# DCDC_Converter.net
KiCad netlist of a schematic drawn in Altium Designer
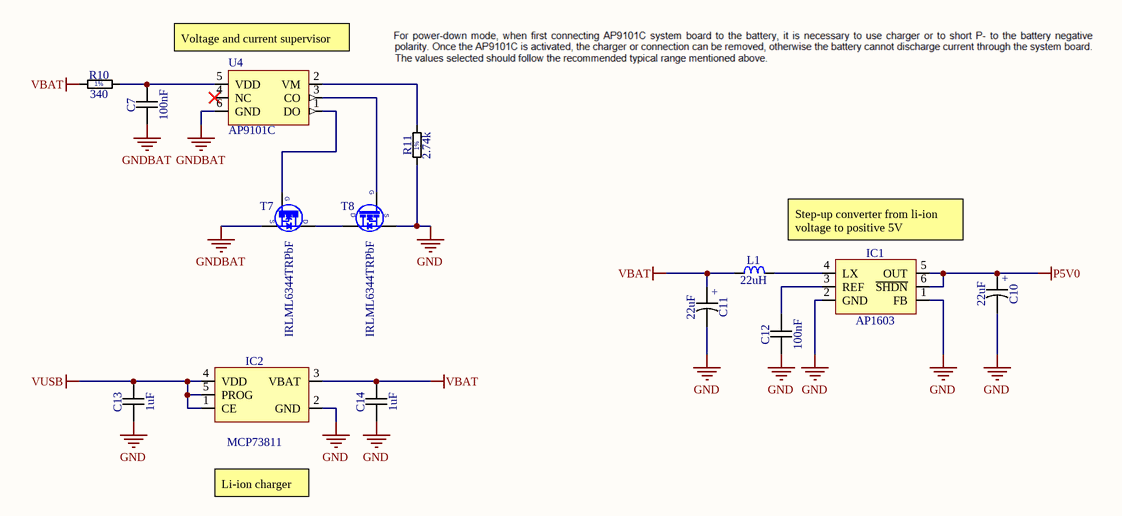
[diagram p0: DCDC_Converter.SchDoc]

(export (version "E")
  (design (tool "Eeschema 10.0.6"))
  (components
    (comp (ref "C7")
      (value "100nF")
      (footprint "CAPC0402X60N")
      (description "Non-polarised capacitor")
      (fields
        (field (name "MANUFACTURER") "GENERIC")
        (field (name "MANUFACTURER PART NUMBER") "CC0402_100NF_16V_10%_X7R")
        (field (name "AUTHOR") "KB")
      )
      (libsource (lib "Capacitors") (part "Capacitor - non polarized"))
    )
    (comp (ref "C10")
      (value "22uF")
      (footprint "CAPC2917X310N")
      (description "Polarised capacitor")
      (fields
        (field (name "MANUFACTURER") "GENERIC")
        (field (name "MANUFACTURER PART NUMBER") "CC2917_22UF_25V_20%_TANTALUM")
        (field (name "AUTHOR") "JK")
      )
      (libsource (lib "Capacitors") (part "Capacitor - polarized"))
    )
    (comp (ref "C11")
      (value "22uF")
      (footprint "CAPC2917X310N")
      (description "Polarised capacitor")
      (fields
        (field (name "MANUFACTURER") "GENERIC")
        (field (name "MANUFACTURER PART NUMBER") "CC2917_22UF_25V_20%_TANTALUM")
        (field (name "AUTHOR") "JK")
      )
      (libsource (lib "Capacitors") (part "Capacitor - polarized"))
    )
    (comp (ref "C12")
      (value "100nF")
      (footprint "CAPC0603X90N")
      (description "Non-polarised capacitor")
      (fields
        (field (name "MANUFACTURER") "GENERIC")
        (field (name "MANUFACTURER PART NUMBER") "CC0603_100NF_16V_10%_X7R")
        (field (name "AUTHOR") "KB")
      )
      (libsource (lib "Capacitors") (part "Capacitor - non polarized"))
    )
    (comp (ref "C13")
      (value "1uF")
      (footprint "CAPC0603X90N")
      (description "Non-polarised capacitor")
      (fields
        (field (name "MANUFACTURER") "GENERIC")
        (field (name "MANUFACTURER PART NUMBER") "CC0603_1UF_6V3_10%_X7R")
        (field (name "AUTHOR") "UN")
      )
      (libsource (lib "Capacitors") (part "Capacitor - non polarized"))
    )
    (comp (ref "C14")
      (value "1uF")
      (footprint "CAPC0603X90N")
      (description "Non-polarised capacitor")
      (fields
        (field (name "MANUFACTURER") "GENERIC")
        (field (name "MANUFACTURER PART NUMBER") "CC0603_1UF_6V3_10%_X7R")
        (field (name "AUTHOR") "UN")
      )
      (libsource (lib "Capacitors") (part "Capacitor - non polarized"))
    )
    (comp (ref "IC1")
      (value "AP1603")
      (footprint "SOT26")
      (description "STEP-UP DC-DC CONVERTER")
      (fields (field (name "MANUFACTURER 1 PART NUMBER") "AP1603WG-7") (field (name "AUTHOR") "JK"))
      (libsource (lib "ICs And Semiconductors") (part "AP1603"))
    )
    (comp (ref "IC2")
      (value "MCP73811")
      (footprint "SOT23-5")
      (description "Simple, Miniature Single-Cell, Fully Integrate d Li-Ion / Li-Polymer Charge Management Controllers")
      (fields (field (name "MANUFACTURER 1 PART NUMBER") "MCP73811T-420I/OT") (field (name "AUTHOR") "JK"))
      (libsource (lib "ICs And Semiconductors") (part "MCP73811"))
    )
    (comp (ref "L1")
      (value "22uH")
      (footprint "INDC1210X150N")
      (description "SMD Inductor")
      (fields
        (field (name "MANUFACTURER") "GENERIC")
        (field (name "MANUFACTURER PART NUMBER") "LQH32MN220K23L")
        (field (name "AUTHOR") "JK")
      )
      (libsource (lib "Inductors") (part "Inductor"))
    )
    (comp (ref "R10")
      (value "340")
      (footprint "RESC0603X60N")
      (description "General Purpose Thick Film Chip Resistor")
      (fields
        (field (name "MANUFACTURER") "GENERIC")
        (field (name "MANUFACTURER PART NUMBER") "R0603_340R_0.0625W 0.1W 0.125W 0.25W 0.5W 1W 0.75W 1W_100PPM")
        (field (name "AUTHOR") "KB")
      )
      (libsource (lib "Resistors") (part "Resistor - 1%"))
    )
    (comp (ref "R11")
      (value "2.74k")
      (footprint "RESC0603X60N")
      (description "General Purpose Thick Film Chip Resistor")
      (fields
        (field (name "MANUFACTURER") "GENERIC")
        (field (name "MANUFACTURER PART NUMBER") "R0603_2K74_0.0625W 0.1W 0.125W 0.25W 0.5W 1W 0.75W 1W_100PPM")
        (field (name "AUTHOR") "KB")
      )
      (libsource (lib "Resistors") (part "Resistor - 1%"))
    )
    (comp (ref "T7")
      (value "IRLML6344TRPbF")
      (footprint "SOT23-3")
      (description "N-MOS 5.0A 29mOhm 30V 2.5V drv capable")
      (fields (field (name "MANUFACTURER 1 PART NUMBER") "IRLML6344TRPBF") (field (name "AUTHOR") "JK"))
      (libsource (lib "") (part "N-MOSFET-D 1G 2S 3D_1"))
    )
    (comp (ref "T8")
      (value "IRLML6344TRPbF")
      (footprint "SOT23-3")
      (description "N-MOS 5.0A 29mOhm 30V 2.5V drv capable")
      (fields (field (name "MANUFACTURER 1 PART NUMBER") "IRLML6344TRPBF") (field (name "AUTHOR") "JK"))
      (libsource (lib "ICs And Semiconductors") (part "N-MOSFET-D 1G 2S 3D"))
    )
    (comp (ref "U4")
      (value "AP9101C")
      (footprint "SOT26")
      (description "SINGLE CHIP SOLUTION FOR 1-CELL Li+ BATTERY PACK")
      (fields (field (name "MANUFACTURER 1 PART NUMBER") "AP9101CK6-AETRG1") (field (name "AUTHOR") "JK"))
      (libsource (lib "ICs And Semiconductors") (part "AP9101C"))
    )
  )
  (nets
    (net (code "1") (name "GND") (class "Default")
      (node (ref "C10") (pin "2") (pinfunction "2_2") (pintype "passive"))
      (node (ref "C11") (pin "2") (pinfunction "2_2") (pintype "passive"))
      (node (ref "C12") (pin "1") (pinfunction "1_1") (pintype "passive"))
      (node (ref "C13") (pin "1") (pinfunction "1_1") (pintype "passive"))
      (node (ref "C14") (pin "1") (pinfunction "1_1") (pintype "passive"))
      (node (ref "IC1") (pin "1") (pinfunction "FB_1") (pintype "power_in"))
      (node (ref "IC1") (pin "2") (pinfunction "GND_2") (pintype "power_in"))
      (node (ref "IC2") (pin "2") (pinfunction "GND_2") (pintype "power_in"))
      (node (ref "R11") (pin "1") (pinfunction "1_1") (pintype "passive"))
      (node (ref "T8") (pin "2") (pinfunction "S_2") (pintype "passive"))
    )
    (net (code "2") (name "GNDBAT") (class "Default")
      (node (ref "C7") (pin "1") (pinfunction "1_1") (pintype "passive"))
      (node (ref "T7") (pin "2") (pinfunction "S_2") (pintype "passive"))
      (node (ref "U4") (pin "6") (pinfunction "GND_6") (pintype "power_in"))
    )
    (net (code "3") (name "Net-(IC1-LX)") (class "Default")
      (node (ref "IC1") (pin "4") (pinfunction "LX_4") (pintype "power_in"))
      (node (ref "L1") (pin "2") (pinfunction "2_2") (pintype "passive"))
    )
    (net (code "4") (name "Net-(IC1-REF)") (class "Default")
      (node (ref "C12") (pin "2") (pinfunction "2_2") (pintype "passive"))
      (node (ref "IC1") (pin "3") (pinfunction "REF_3") (pintype "power_in"))
    )
    (net (code "5") (name "Net-(T7-D)") (class "Default")
      (node (ref "T7") (pin "3") (pinfunction "D_3") (pintype "passive"))
      (node (ref "T8") (pin "3") (pinfunction "D_3") (pintype "passive"))
    )
    (net (code "6") (name "Net-(T7-G)") (class "Default")
      (node (ref "T7") (pin "1") (pinfunction "G_1") (pintype "passive"))
      (node (ref "U4") (pin "1") (pinfunction "DO_1") (pintype "output"))
    )
    (net (code "7") (name "Net-(T8-G)") (class "Default")
      (node (ref "T8") (pin "1") (pinfunction "G_1") (pintype "passive"))
      (node (ref "U4") (pin "3") (pinfunction "CO_3") (pintype "output"))
    )
    (net (code "8") (name "Net-(U4-VDD)") (class "Default")
      (node (ref "C7") (pin "2") (pinfunction "2_2") (pintype "passive"))
      (node (ref "R10") (pin "2") (pinfunction "2_2") (pintype "passive"))
      (node (ref "U4") (pin "5") (pinfunction "VDD_5") (pintype "power_in"))
    )
    (net (code "9") (name "Net-(U4-VM)") (class "Default")
      (node (ref "R11") (pin "2") (pinfunction "2_2") (pintype "passive"))
      (node (ref "U4") (pin "2") (pinfunction "VM_2") (pintype "passive"))
    )
    (net (code "10") (name "P5V0") (class "Default")
      (node (ref "C10") (pin "1") (pinfunction "1_1") (pintype "passive"))
      (node (ref "IC1") (pin "5") (pinfunction "OUT_5") (pintype "power_in"))
      (node (ref "IC1") (pin "6") (pinfunction "~{SHDN}_6") (pintype "power_in"))
    )
    (net (code "11") (name "VBAT") (class "Default")
      (node (ref "C11") (pin "1") (pinfunction "1_1") (pintype "passive"))
      (node (ref "C14") (pin "2") (pinfunction "2_2") (pintype "passive"))
      (node (ref "IC2") (pin "3") (pinfunction "VBAT_3") (pintype "power_in"))
      (node (ref "L1") (pin "1") (pinfunction "1_1") (pintype "passive"))
      (node (ref "R10") (pin "1") (pinfunction "1_1") (pintype "passive"))
    )
    (net (code "12") (name "VUSB") (class "Default")
      (node (ref "C13") (pin "2") (pinfunction "2_2") (pintype "passive"))
      (node (ref "IC2") (pin "1") (pinfunction "CE_1") (pintype "power_in"))
      (node (ref "IC2") (pin "4") (pinfunction "VDD_4") (pintype "power_in"))
      (node (ref "IC2") (pin "5") (pinfunction "PROG_5") (pintype "power_in"))
    )
    (net (code "13") (name "unconnected-(U4-NC-Pad4)") (class "Default")
      (node (ref "U4") (pin "4") (pinfunction "NC_4") (pintype "passive+no_connect"))
    )
  )
)
